# Bus_Definition_V1_2.net
KiCad netlist of a schematic drawn in EAGLE
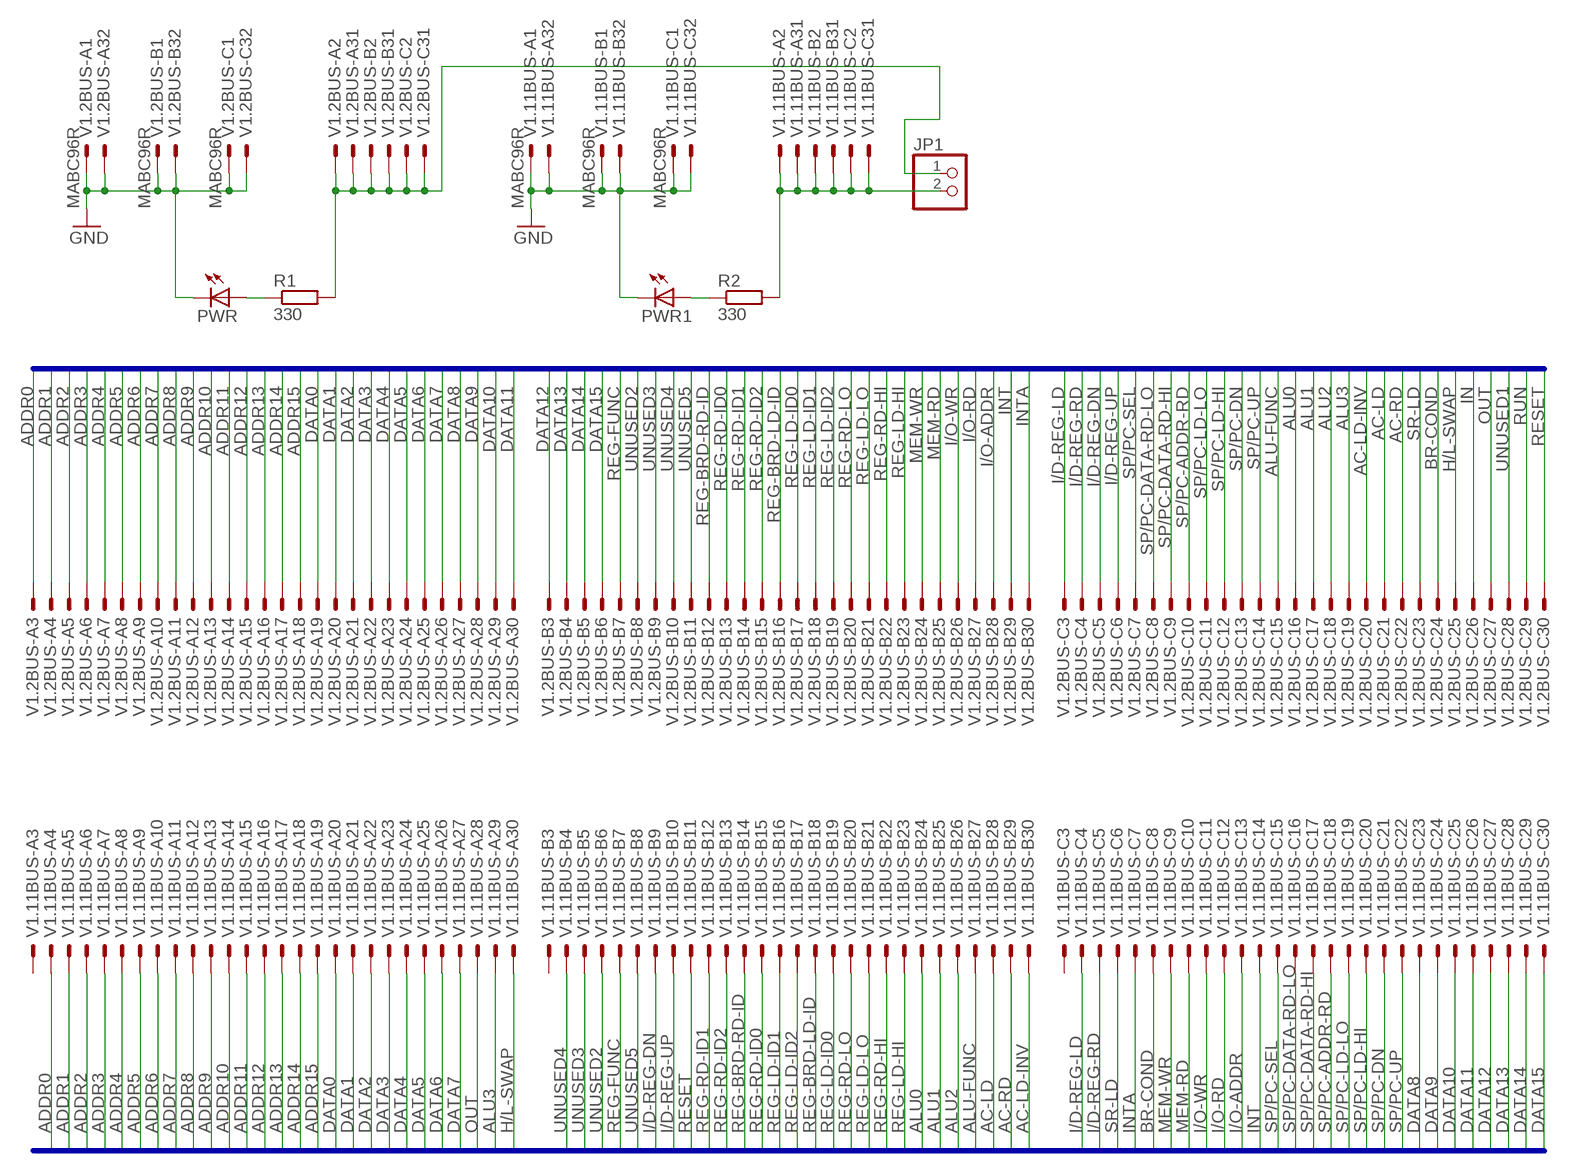
[diagram p0: schematic, sheet 1]

(export (version "E")
  (design (tool "Eeschema 10.0.6"))
  (components
    (comp (ref "JP1")
      (value "PINHD-1X2")
      (footprint "eagle-import:1X02")
      (libsource (lib "eagle-import") (part "PINHD-1X2"))
    )
    (comp (ref "PWR")
      (value "LED5MM")
      (footprint "eagle-import:LED5MM")
      (libsource (lib "eagle-import") (part "LED5MM"))
    )
    (comp (ref "PWR1")
      (value "LED5MM")
      (footprint "eagle-import:LED5MM")
      (libsource (lib "eagle-import") (part "LED5MM"))
    )
    (comp (ref "R1")
      (value "330")
      (footprint "eagle-import:0207_10")
      (libsource (lib "eagle-import") (part "R0207/10"))
    )
    (comp (ref "R2")
      (value "330")
      (footprint "eagle-import:0207_10")
      (libsource (lib "eagle-import") (part "R0207/10"))
    )
    (comp (ref "V1.2BUS")
      (value "MABC96R")
      (footprint "eagle-import:MABC96R")
      (libsource (lib "eagle-import") (part "MABC96R"))
    )
    (comp (ref "V1.11BUS")
      (value "MABC96R")
      (footprint "eagle-import:MABC96R")
      (libsource (lib "eagle-import") (part "MABC96R"))
    )
  )
  (nets
    (net (code "1") (name "/AC-LD") (class "Default")
      (node (ref "V1.11BUS") (pin "B28") (pinfunction "S_B28") (pintype "passive"))
      (node (ref "V1.2BUS") (pin "C21") (pinfunction "S_C21") (pintype "passive"))
    )
    (net (code "2") (name "/AC-LD-INV") (class "Default")
      (node (ref "V1.11BUS") (pin "B30") (pinfunction "S_B30") (pintype "passive"))
      (node (ref "V1.2BUS") (pin "C20") (pinfunction "S_C20") (pintype "passive"))
    )
    (net (code "3") (name "/AC-RD") (class "Default")
      (node (ref "V1.11BUS") (pin "B29") (pinfunction "S_B29") (pintype "passive"))
      (node (ref "V1.2BUS") (pin "C22") (pinfunction "S_C22") (pintype "passive"))
    )
    (net (code "4") (name "/ADDR0") (class "Default")
      (node (ref "V1.11BUS") (pin "A4") (pinfunction "S_A4") (pintype "passive"))
      (node (ref "V1.2BUS") (pin "A3") (pinfunction "S_A3") (pintype "passive"))
    )
    (net (code "5") (name "/ADDR1") (class "Default")
      (node (ref "V1.11BUS") (pin "A5") (pinfunction "S_A5") (pintype "passive"))
      (node (ref "V1.2BUS") (pin "A4") (pinfunction "S_A4") (pintype "passive"))
    )
    (net (code "6") (name "/ADDR2") (class "Default")
      (node (ref "V1.11BUS") (pin "A6") (pinfunction "S_A6") (pintype "passive"))
      (node (ref "V1.2BUS") (pin "A5") (pinfunction "S_A5") (pintype "passive"))
    )
    (net (code "7") (name "/ADDR3") (class "Default")
      (node (ref "V1.11BUS") (pin "A7") (pinfunction "S_A7") (pintype "passive"))
      (node (ref "V1.2BUS") (pin "A6") (pinfunction "S_A6") (pintype "passive"))
    )
    (net (code "8") (name "/ADDR4") (class "Default")
      (node (ref "V1.11BUS") (pin "A8") (pinfunction "S_A8") (pintype "passive"))
      (node (ref "V1.2BUS") (pin "A7") (pinfunction "S_A7") (pintype "passive"))
    )
    (net (code "9") (name "/ADDR5") (class "Default")
      (node (ref "V1.11BUS") (pin "A9") (pinfunction "S_A9") (pintype "passive"))
      (node (ref "V1.2BUS") (pin "A8") (pinfunction "S_A8") (pintype "passive"))
    )
    (net (code "10") (name "/ADDR6") (class "Default")
      (node (ref "V1.11BUS") (pin "A10") (pinfunction "S_A10") (pintype "passive"))
      (node (ref "V1.2BUS") (pin "A9") (pinfunction "S_A9") (pintype "passive"))
    )
    (net (code "11") (name "/ADDR7") (class "Default")
      (node (ref "V1.11BUS") (pin "A11") (pinfunction "S_A11") (pintype "passive"))
      (node (ref "V1.2BUS") (pin "A10") (pinfunction "S_A10") (pintype "passive"))
    )
    (net (code "12") (name "/ADDR8") (class "Default")
      (node (ref "V1.11BUS") (pin "A12") (pinfunction "S_A12") (pintype "passive"))
      (node (ref "V1.2BUS") (pin "A11") (pinfunction "S_A11") (pintype "passive"))
    )
    (net (code "13") (name "/ADDR9") (class "Default")
      (node (ref "V1.11BUS") (pin "A13") (pinfunction "S_A13") (pintype "passive"))
      (node (ref "V1.2BUS") (pin "A12") (pinfunction "S_A12") (pintype "passive"))
    )
    (net (code "14") (name "/ADDR10") (class "Default")
      (node (ref "V1.11BUS") (pin "A14") (pinfunction "S_A14") (pintype "passive"))
      (node (ref "V1.2BUS") (pin "A13") (pinfunction "S_A13") (pintype "passive"))
    )
    (net (code "15") (name "/ADDR11") (class "Default")
      (node (ref "V1.11BUS") (pin "A15") (pinfunction "S_A15") (pintype "passive"))
      (node (ref "V1.2BUS") (pin "A14") (pinfunction "S_A14") (pintype "passive"))
    )
    (net (code "16") (name "/ADDR12") (class "Default")
      (node (ref "V1.11BUS") (pin "A16") (pinfunction "S_A16") (pintype "passive"))
      (node (ref "V1.2BUS") (pin "A15") (pinfunction "S_A15") (pintype "passive"))
    )
    (net (code "17") (name "/ADDR13") (class "Default")
      (node (ref "V1.11BUS") (pin "A17") (pinfunction "S_A17") (pintype "passive"))
      (node (ref "V1.2BUS") (pin "A16") (pinfunction "S_A16") (pintype "passive"))
    )
    (net (code "18") (name "/ADDR14") (class "Default")
      (node (ref "V1.11BUS") (pin "A18") (pinfunction "S_A18") (pintype "passive"))
      (node (ref "V1.2BUS") (pin "A17") (pinfunction "S_A17") (pintype "passive"))
    )
    (net (code "19") (name "/ADDR15") (class "Default")
      (node (ref "V1.11BUS") (pin "A19") (pinfunction "S_A19") (pintype "passive"))
      (node (ref "V1.2BUS") (pin "A18") (pinfunction "S_A18") (pintype "passive"))
    )
    (net (code "20") (name "/ALU-FUNC") (class "Default")
      (node (ref "V1.11BUS") (pin "B27") (pinfunction "S_B27") (pintype "passive"))
      (node (ref "V1.2BUS") (pin "C15") (pinfunction "S_C15") (pintype "passive"))
    )
    (net (code "21") (name "/ALU0") (class "Default")
      (node (ref "V1.11BUS") (pin "B24") (pinfunction "S_B24") (pintype "passive"))
      (node (ref "V1.2BUS") (pin "C16") (pinfunction "S_C16") (pintype "passive"))
    )
    (net (code "22") (name "/ALU1") (class "Default")
      (node (ref "V1.11BUS") (pin "B25") (pinfunction "S_B25") (pintype "passive"))
      (node (ref "V1.2BUS") (pin "C17") (pinfunction "S_C17") (pintype "passive"))
    )
    (net (code "23") (name "/ALU2") (class "Default")
      (node (ref "V1.11BUS") (pin "B26") (pinfunction "S_B26") (pintype "passive"))
      (node (ref "V1.2BUS") (pin "C18") (pinfunction "S_C18") (pintype "passive"))
    )
    (net (code "24") (name "/ALU3") (class "Default")
      (node (ref "V1.11BUS") (pin "A29") (pinfunction "S_A29") (pintype "passive"))
      (node (ref "V1.2BUS") (pin "C19") (pinfunction "S_C19") (pintype "passive"))
    )
    (net (code "25") (name "/BR-COND") (class "Default")
      (node (ref "V1.11BUS") (pin "C8") (pinfunction "S_C8") (pintype "passive"))
      (node (ref "V1.2BUS") (pin "C24") (pinfunction "S_C24") (pintype "passive"))
    )
    (net (code "26") (name "/DATA0") (class "Default")
      (node (ref "V1.11BUS") (pin "A20") (pinfunction "S_A20") (pintype "passive"))
      (node (ref "V1.2BUS") (pin "A19") (pinfunction "S_A19") (pintype "passive"))
    )
    (net (code "27") (name "/DATA1") (class "Default")
      (node (ref "V1.11BUS") (pin "A21") (pinfunction "S_A21") (pintype "passive"))
      (node (ref "V1.2BUS") (pin "A20") (pinfunction "S_A20") (pintype "passive"))
    )
    (net (code "28") (name "/DATA2") (class "Default")
      (node (ref "V1.11BUS") (pin "A22") (pinfunction "S_A22") (pintype "passive"))
      (node (ref "V1.2BUS") (pin "A21") (pinfunction "S_A21") (pintype "passive"))
    )
    (net (code "29") (name "/DATA3") (class "Default")
      (node (ref "V1.11BUS") (pin "A23") (pinfunction "S_A23") (pintype "passive"))
      (node (ref "V1.2BUS") (pin "A22") (pinfunction "S_A22") (pintype "passive"))
    )
    (net (code "30") (name "/DATA4") (class "Default")
      (node (ref "V1.11BUS") (pin "A24") (pinfunction "S_A24") (pintype "passive"))
      (node (ref "V1.2BUS") (pin "A23") (pinfunction "S_A23") (pintype "passive"))
    )
    (net (code "31") (name "/DATA5") (class "Default")
      (node (ref "V1.11BUS") (pin "A25") (pinfunction "S_A25") (pintype "passive"))
      (node (ref "V1.2BUS") (pin "A24") (pinfunction "S_A24") (pintype "passive"))
    )
    (net (code "32") (name "/DATA6") (class "Default")
      (node (ref "V1.11BUS") (pin "A26") (pinfunction "S_A26") (pintype "passive"))
      (node (ref "V1.2BUS") (pin "A25") (pinfunction "S_A25") (pintype "passive"))
    )
    (net (code "33") (name "/DATA7") (class "Default")
      (node (ref "V1.11BUS") (pin "A27") (pinfunction "S_A27") (pintype "passive"))
      (node (ref "V1.2BUS") (pin "A26") (pinfunction "S_A26") (pintype "passive"))
    )
    (net (code "34") (name "/DATA8") (class "Default")
      (node (ref "V1.11BUS") (pin "C23") (pinfunction "S_C23") (pintype "passive"))
      (node (ref "V1.2BUS") (pin "A27") (pinfunction "S_A27") (pintype "passive"))
    )
    (net (code "35") (name "/DATA9") (class "Default")
      (node (ref "V1.11BUS") (pin "C24") (pinfunction "S_C24") (pintype "passive"))
      (node (ref "V1.2BUS") (pin "A28") (pinfunction "S_A28") (pintype "passive"))
    )
    (net (code "36") (name "/DATA10") (class "Default")
      (node (ref "V1.11BUS") (pin "C25") (pinfunction "S_C25") (pintype "passive"))
      (node (ref "V1.2BUS") (pin "A29") (pinfunction "S_A29") (pintype "passive"))
    )
    (net (code "37") (name "/DATA11") (class "Default")
      (node (ref "V1.11BUS") (pin "C26") (pinfunction "S_C26") (pintype "passive"))
      (node (ref "V1.2BUS") (pin "A30") (pinfunction "S_A30") (pintype "passive"))
    )
    (net (code "38") (name "/DATA12") (class "Default")
      (node (ref "V1.11BUS") (pin "C27") (pinfunction "S_C27") (pintype "passive"))
      (node (ref "V1.2BUS") (pin "B3") (pinfunction "S_B3") (pintype "passive"))
    )
    (net (code "39") (name "/DATA13") (class "Default")
      (node (ref "V1.11BUS") (pin "C28") (pinfunction "S_C28") (pintype "passive"))
      (node (ref "V1.2BUS") (pin "B4") (pinfunction "S_B4") (pintype "passive"))
    )
    (net (code "40") (name "/DATA14") (class "Default")
      (node (ref "V1.11BUS") (pin "C29") (pinfunction "S_C29") (pintype "passive"))
      (node (ref "V1.2BUS") (pin "B5") (pinfunction "S_B5") (pintype "passive"))
    )
    (net (code "41") (name "/DATA15") (class "Default")
      (node (ref "V1.11BUS") (pin "C30") (pinfunction "S_C30") (pintype "passive"))
      (node (ref "V1.2BUS") (pin "B6") (pinfunction "S_B6") (pintype "passive"))
    )
    (net (code "42") (name "/H{slash}L-SWAP") (class "Default")
      (node (ref "V1.11BUS") (pin "A30") (pinfunction "S_A30") (pintype "passive"))
      (node (ref "V1.2BUS") (pin "C25") (pinfunction "S_C25") (pintype "passive"))
    )
    (net (code "43") (name "/IN") (class "Default")
      (node (ref "V1.2BUS") (pin "C26") (pinfunction "S_C26") (pintype "passive"))
    )
    (net (code "44") (name "/INT") (class "Default")
      (node (ref "V1.11BUS") (pin "C14") (pinfunction "S_C14") (pintype "passive"))
      (node (ref "V1.2BUS") (pin "B29") (pinfunction "S_B29") (pintype "passive"))
    )
    (net (code "45") (name "/INTA") (class "Default")
      (node (ref "V1.11BUS") (pin "C7") (pinfunction "S_C7") (pintype "passive"))
      (node (ref "V1.2BUS") (pin "B30") (pinfunction "S_B30") (pintype "passive"))
    )
    (net (code "46") (name "/I{slash}D-REG-DN") (class "Default")
      (node (ref "V1.11BUS") (pin "B9") (pinfunction "S_B9") (pintype "passive"))
      (node (ref "V1.2BUS") (pin "C5") (pinfunction "S_C5") (pintype "passive"))
    )
    (net (code "47") (name "/I{slash}D-REG-LD") (class "Default")
      (node (ref "V1.11BUS") (pin "C4") (pinfunction "S_C4") (pintype "passive"))
      (node (ref "V1.2BUS") (pin "C3") (pinfunction "S_C3") (pintype "passive"))
    )
    (net (code "48") (name "/I{slash}D-REG-RD") (class "Default")
      (node (ref "V1.11BUS") (pin "C5") (pinfunction "S_C5") (pintype "passive"))
      (node (ref "V1.2BUS") (pin "C4") (pinfunction "S_C4") (pintype "passive"))
    )
    (net (code "49") (name "/I{slash}D-REG-UP") (class "Default")
      (node (ref "V1.11BUS") (pin "B10") (pinfunction "S_B10") (pintype "passive"))
      (node (ref "V1.2BUS") (pin "C6") (pinfunction "S_C6") (pintype "passive"))
    )
    (net (code "50") (name "/I{slash}O-ADDR") (class "Default")
      (node (ref "V1.11BUS") (pin "C13") (pinfunction "S_C13") (pintype "passive"))
      (node (ref "V1.2BUS") (pin "B28") (pinfunction "S_B28") (pintype "passive"))
    )
    (net (code "51") (name "/I{slash}O-RD") (class "Default")
      (node (ref "V1.11BUS") (pin "C12") (pinfunction "S_C12") (pintype "passive"))
      (node (ref "V1.2BUS") (pin "B27") (pinfunction "S_B27") (pintype "passive"))
    )
    (net (code "52") (name "/I{slash}O-WR") (class "Default")
      (node (ref "V1.11BUS") (pin "C11") (pinfunction "S_C11") (pintype "passive"))
      (node (ref "V1.2BUS") (pin "B26") (pinfunction "S_B26") (pintype "passive"))
    )
    (net (code "53") (name "/MEM-RD") (class "Default")
      (node (ref "V1.11BUS") (pin "C10") (pinfunction "S_C10") (pintype "passive"))
      (node (ref "V1.2BUS") (pin "B25") (pinfunction "S_B25") (pintype "passive"))
    )
    (net (code "54") (name "/MEM-WR") (class "Default")
      (node (ref "V1.11BUS") (pin "C9") (pinfunction "S_C9") (pintype "passive"))
      (node (ref "V1.2BUS") (pin "B24") (pinfunction "S_B24") (pintype "passive"))
    )
    (net (code "55") (name "/OUT") (class "Default")
      (node (ref "V1.11BUS") (pin "A28") (pinfunction "S_A28") (pintype "passive"))
      (node (ref "V1.2BUS") (pin "C27") (pinfunction "S_C27") (pintype "passive"))
    )
    (net (code "56") (name "/REG-BRD-LD-ID") (class "Default")
      (node (ref "V1.11BUS") (pin "B18") (pinfunction "S_B18") (pintype "passive"))
      (node (ref "V1.2BUS") (pin "B16") (pinfunction "S_B16") (pintype "passive"))
    )
    (net (code "57") (name "/REG-BRD-RD-ID") (class "Default")
      (node (ref "V1.11BUS") (pin "B14") (pinfunction "S_B14") (pintype "passive"))
      (node (ref "V1.2BUS") (pin "B12") (pinfunction "S_B12") (pintype "passive"))
    )
    (net (code "58") (name "/REG-FUNC") (class "Default")
      (node (ref "V1.11BUS") (pin "B7") (pinfunction "S_B7") (pintype "passive"))
      (node (ref "V1.2BUS") (pin "B7") (pinfunction "S_B7") (pintype "passive"))
    )
    (net (code "59") (name "/REG-LD-HI") (class "Default")
      (node (ref "V1.11BUS") (pin "B23") (pinfunction "S_B23") (pintype "passive"))
      (node (ref "V1.2BUS") (pin "B23") (pinfunction "S_B23") (pintype "passive"))
    )
    (net (code "60") (name "/REG-LD-ID0") (class "Default")
      (node (ref "V1.11BUS") (pin "B19") (pinfunction "S_B19") (pintype "passive"))
      (node (ref "V1.2BUS") (pin "B17") (pinfunction "S_B17") (pintype "passive"))
    )
    (net (code "61") (name "/REG-LD-ID1") (class "Default")
      (node (ref "V1.11BUS") (pin "B16") (pinfunction "S_B16") (pintype "passive"))
      (node (ref "V1.2BUS") (pin "B18") (pinfunction "S_B18") (pintype "passive"))
    )
    (net (code "62") (name "/REG-LD-ID2") (class "Default")
      (node (ref "V1.11BUS") (pin "B17") (pinfunction "S_B17") (pintype "passive"))
      (node (ref "V1.2BUS") (pin "B19") (pinfunction "S_B19") (pintype "passive"))
    )
    (net (code "63") (name "/REG-LD-LO") (class "Default")
      (node (ref "V1.11BUS") (pin "B21") (pinfunction "S_B21") (pintype "passive"))
      (node (ref "V1.2BUS") (pin "B21") (pinfunction "S_B21") (pintype "passive"))
    )
    (net (code "64") (name "/REG-RD-HI") (class "Default")
      (node (ref "V1.11BUS") (pin "B22") (pinfunction "S_B22") (pintype "passive"))
      (node (ref "V1.2BUS") (pin "B22") (pinfunction "S_B22") (pintype "passive"))
    )
    (net (code "65") (name "/REG-RD-ID0") (class "Default")
      (node (ref "V1.11BUS") (pin "B15") (pinfunction "S_B15") (pintype "passive"))
      (node (ref "V1.2BUS") (pin "B13") (pinfunction "S_B13") (pintype "passive"))
    )
    (net (code "66") (name "/REG-RD-ID1") (class "Default")
      (node (ref "V1.11BUS") (pin "B12") (pinfunction "S_B12") (pintype "passive"))
      (node (ref "V1.2BUS") (pin "B14") (pinfunction "S_B14") (pintype "passive"))
    )
    (net (code "67") (name "/REG-RD-ID2") (class "Default")
      (node (ref "V1.11BUS") (pin "B13") (pinfunction "S_B13") (pintype "passive"))
      (node (ref "V1.2BUS") (pin "B15") (pinfunction "S_B15") (pintype "passive"))
    )
    (net (code "68") (name "/REG-RD-LO") (class "Default")
      (node (ref "V1.11BUS") (pin "B20") (pinfunction "S_B20") (pintype "passive"))
      (node (ref "V1.2BUS") (pin "B20") (pinfunction "S_B20") (pintype "passive"))
    )
    (net (code "69") (name "/RESET") (class "Default")
      (node (ref "V1.11BUS") (pin "B11") (pinfunction "S_B11") (pintype "passive"))
      (node (ref "V1.2BUS") (pin "C30") (pinfunction "S_C30") (pintype "passive"))
    )
    (net (code "70") (name "/RUN") (class "Default")
      (node (ref "V1.2BUS") (pin "C29") (pinfunction "S_C29") (pintype "passive"))
    )
    (net (code "71") (name "/SP{slash}PC-ADDR-RD") (class "Default")
      (node (ref "V1.11BUS") (pin "C18") (pinfunction "S_C18") (pintype "passive"))
      (node (ref "V1.2BUS") (pin "C10") (pinfunction "S_C10") (pintype "passive"))
    )
    (net (code "72") (name "/SP{slash}PC-DATA-RD-HI") (class "Default")
      (node (ref "V1.11BUS") (pin "C17") (pinfunction "S_C17") (pintype "passive"))
      (node (ref "V1.2BUS") (pin "C9") (pinfunction "S_C9") (pintype "passive"))
    )
    (net (code "73") (name "/SP{slash}PC-DATA-RD-LO") (class "Default")
      (node (ref "V1.11BUS") (pin "C16") (pinfunction "S_C16") (pintype "passive"))
      (node (ref "V1.2BUS") (pin "C8") (pinfunction "S_C8") (pintype "passive"))
    )
    (net (code "74") (name "/SP{slash}PC-DN") (class "Default")
      (node (ref "V1.11BUS") (pin "C21") (pinfunction "S_C21") (pintype "passive"))
      (node (ref "V1.2BUS") (pin "C13") (pinfunction "S_C13") (pintype "passive"))
    )
    (net (code "75") (name "/SP{slash}PC-LD-HI") (class "Default")
      (node (ref "V1.11BUS") (pin "C20") (pinfunction "S_C20") (pintype "passive"))
      (node (ref "V1.2BUS") (pin "C12") (pinfunction "S_C12") (pintype "passive"))
    )
    (net (code "76") (name "/SP{slash}PC-LD-LO") (class "Default")
      (node (ref "V1.11BUS") (pin "C19") (pinfunction "S_C19") (pintype "passive"))
      (node (ref "V1.2BUS") (pin "C11") (pinfunction "S_C11") (pintype "passive"))
    )
    (net (code "77") (name "/SP{slash}PC-SEL") (class "Default")
      (node (ref "V1.11BUS") (pin "C15") (pinfunction "S_C15") (pintype "passive"))
      (node (ref "V1.2BUS") (pin "C7") (pinfunction "S_C7") (pintype "passive"))
    )
    (net (code "78") (name "/SP{slash}PC-UP") (class "Default")
      (node (ref "V1.11BUS") (pin "C22") (pinfunction "S_C22") (pintype "passive"))
      (node (ref "V1.2BUS") (pin "C14") (pinfunction "S_C14") (pintype "passive"))
    )
    (net (code "79") (name "/SR-LD") (class "Default")
      (node (ref "V1.11BUS") (pin "C6") (pinfunction "S_C6") (pintype "passive"))
      (node (ref "V1.2BUS") (pin "C23") (pinfunction "S_C23") (pintype "passive"))
    )
    (net (code "80") (name "/UNUSED1") (class "Default")
      (node (ref "V1.2BUS") (pin "C28") (pinfunction "S_C28") (pintype "passive"))
    )
    (net (code "81") (name "/UNUSED2") (class "Default")
      (node (ref "V1.11BUS") (pin "B6") (pinfunction "S_B6") (pintype "passive"))
      (node (ref "V1.2BUS") (pin "B8") (pinfunction "S_B8") (pintype "passive"))
    )
    (net (code "82") (name "/UNUSED3") (class "Default")
      (node (ref "V1.11BUS") (pin "B5") (pinfunction "S_B5") (pintype "passive"))
      (node (ref "V1.2BUS") (pin "B9") (pinfunction "S_B9") (pintype "passive"))
    )
    (net (code "83") (name "/UNUSED4") (class "Default")
      (node (ref "V1.11BUS") (pin "B4") (pinfunction "S_B4") (pintype "passive"))
      (node (ref "V1.2BUS") (pin "B10") (pinfunction "S_B10") (pintype "passive"))
    )
    (net (code "84") (name "/UNUSED5") (class "Default")
      (node (ref "V1.11BUS") (pin "B8") (pinfunction "S_B8") (pintype "passive"))
      (node (ref "V1.2BUS") (pin "B11") (pinfunction "S_B11") (pintype "passive"))
    )
    (net (code "85") (name "GND") (class "Default")
      (node (ref "PWR") (pin "K") (pinfunction "C_K") (pintype "passive"))
      (node (ref "PWR1") (pin "K") (pinfunction "C_K") (pintype "passive"))
      (node (ref "V1.11BUS") (pin "A1") (pinfunction "S_A1") (pintype "passive"))
      (node (ref "V1.11BUS") (pin "A32") (pinfunction "S_A32") (pintype "passive"))
      (node (ref "V1.11BUS") (pin "B1") (pinfunction "S_B1") (pintype "passive"))
      (node (ref "V1.11BUS") (pin "B32") (pinfunction "S_B32") (pintype "passive"))
      (node (ref "V1.11BUS") (pin "C1") (pinfunction "S_C1") (pintype "passive"))
      (node (ref "V1.11BUS") (pin "C32") (pinfunction "S_C32") (pintype "passive"))
      (node (ref "V1.2BUS") (pin "A1") (pinfunction "S_A1") (pintype "passive"))
      (node (ref "V1.2BUS") (pin "A32") (pinfunction "S_A32") (pintype "passive"))
      (node (ref "V1.2BUS") (pin "B1") (pinfunction "S_B1") (pintype "passive"))
      (node (ref "V1.2BUS") (pin "B32") (pinfunction "S_B32") (pintype "passive"))
      (node (ref "V1.2BUS") (pin "C1") (pinfunction "S_C1") (pintype "passive"))
      (node (ref "V1.2BUS") (pin "C32") (pinfunction "S_C32") (pintype "passive"))
    )
    (net (code "86") (name "Net-(PWR-PadA)") (class "Default")
      (node (ref "PWR") (pin "A") (pinfunction "A_A") (pintype "passive"))
      (node (ref "R1") (pin "1") (pinfunction "1_1") (pintype "passive"))
    )
    (net (code "87") (name "Net-(PWR1-PadA)") (class "Default")
      (node (ref "PWR1") (pin "A") (pinfunction "A_A") (pintype "passive"))
      (node (ref "R2") (pin "1") (pinfunction "1_1") (pintype "passive"))
    )
    (net (code "88") (name "Net-(V1.2BUSAR-S)") (class "Default")
      (node (ref "JP1") (pin "1") (pinfunction "1_1") (pintype "passive"))
      (node (ref "R1") (pin "2") (pinfunction "2_2") (pintype "passive"))
      (node (ref "V1.2BUS") (pin "A2") (pinfunction "S_A2") (pintype "passive"))
      (node (ref "V1.2BUS") (pin "A31") (pinfunction "S_A31") (pintype "passive"))
      (node (ref "V1.2BUS") (pin "B2") (pinfunction "S_B2") (pintype "passive"))
      (node (ref "V1.2BUS") (pin "B31") (pinfunction "S_B31") (pintype "passive"))
      (node (ref "V1.2BUS") (pin "C2") (pinfunction "S_C2") (pintype "passive"))
      (node (ref "V1.2BUS") (pin "C31") (pinfunction "S_C31") (pintype "passive"))
    )
    (net (code "89") (name "Net-(V1.11BUSAR-S)") (class "Default")
      (node (ref "JP1") (pin "2") (pinfunction "2_2") (pintype "passive"))
      (node (ref "R2") (pin "2") (pinfunction "2_2") (pintype "passive"))
      (node (ref "V1.11BUS") (pin "A2") (pinfunction "S_A2") (pintype "passive"))
      (node (ref "V1.11BUS") (pin "A31") (pinfunction "S_A31") (pintype "passive"))
      (node (ref "V1.11BUS") (pin "B2") (pinfunction "S_B2") (pintype "passive"))
      (node (ref "V1.11BUS") (pin "B31") (pinfunction "S_B31") (pintype "passive"))
      (node (ref "V1.11BUS") (pin "C2") (pinfunction "S_C2") (pintype "passive"))
      (node (ref "V1.11BUS") (pin "C31") (pinfunction "S_C31") (pintype "passive"))
    )
    (net (code "90") (name "unconnected-(V1.11BUSBC-S-PadB3)") (class "Default")
      (node (ref "V1.11BUS") (pin "B3") (pinfunction "S_B3") (pintype "passive"))
    )
    (net (code "91") (name "unconnected-(V1.11BUSCI-S-PadC3)") (class "Default")
      (node (ref "V1.11BUS") (pin "C3") (pinfunction "S_C3") (pintype "passive"))
    )
    (net (code "92") (name "unconnected-(V1.11BUSW-S-PadA3)") (class "Default")
      (node (ref "V1.11BUS") (pin "A3") (pinfunction "S_A3") (pintype "passive"))
    )
  )
)
